# Boost_CNV.net
KiCad netlist of a schematic drawn in Altium Designer
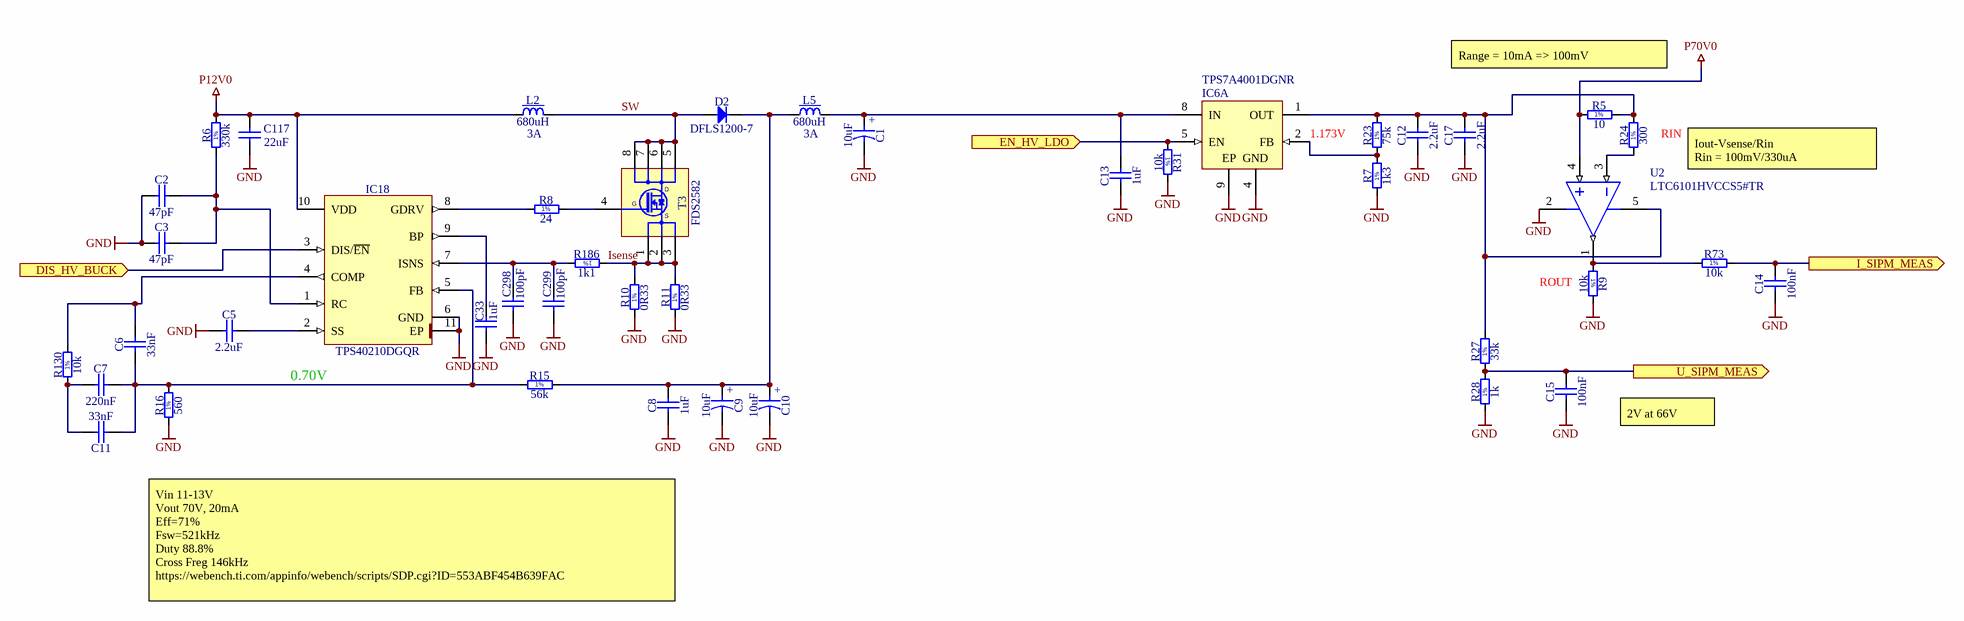
[diagram p0: Boost_CNV.SchDoc]

(export (version "E")
  (design (tool "Eeschema 10.0.6"))
  (components
    (comp (ref "C1")
      (value "10uF")
      (footprint "CAPAE830X1020N")
      (description "10uF, 100V, 1.5R")
      (fields
        (field (name "PART NUMBER") "CAE830-1020_10UF_100V_20%")
        (field (name "VOLTAGE") "100V")
        (field (name "AUTHOR") "CERN DEM JLC")
      )
      (libsource (lib "LIBRARY_SCH") (part "CAP_ELECTRO_SMD_F_10u_100V"))
    )
    (comp (ref "C2")
      (value "47pF")
      (footprint "CAPC1005X55N")
      (description "Non-polarised capacitor")
      (fields
        (field (name "PART NUMBER") "CC0402_47PF_50V_5%_C0G")
        (field (name "VOLTAGE") "50V")
        (field (name "AUTHOR") "CERN DEM JLC")
      )
      (libsource (lib "Capacitors") (part "Capacitor - non polarized"))
    )
    (comp (ref "C3")
      (value "47pF")
      (footprint "CAPC1005X55N")
      (description "Non-polarised capacitor")
      (fields
        (field (name "PART NUMBER") "CC0402_47PF_50V_5%_C0G")
        (field (name "VOLTAGE") "50V")
        (field (name "AUTHOR") "CERN DEM JLC")
      )
      (libsource (lib "Capacitors") (part "Capacitor - non polarized"))
    )
    (comp (ref "C5")
      (value "2.2uF")
      (footprint "CAPC2012X135N")
      (description "Non-polarised capacitor")
      (fields
        (field (name "PART NUMBER") "CC0805_2.2UF_16V_10%_X7R")
        (field (name "VOLTAGE") "16V")
        (field (name "AUTHOR") "CERN DEM JLC")
      )
      (libsource (lib "Capacitors") (part "Capacitor - non polarized"))
    )
    (comp (ref "C6")
      (value "33nF")
      (footprint "CAPC2012X135N")
      (description "Non-polarised capacitor")
      (fields
        (field (name "PART NUMBER") "CC0805_33NF_25V_10%_X7R")
        (field (name "VOLTAGE") "25V")
        (field (name "AUTHOR") "CERN DEM JLC")
      )
      (libsource (lib "Capacitors") (part "Capacitor - non polarized"))
    )
    (comp (ref "C7")
      (value "220nF")
      (footprint "CAPC2012X135N")
      (description "Non-polarised capacitor")
      (fields
        (field (name "PART NUMBER") "CC0805_220NF_50V_10%_X7R")
        (field (name "VOLTAGE") "50V")
        (field (name "AUTHOR") "CERN DEM JLC")
      )
      (libsource (lib "Capacitors") (part "Capacitor - non polarized"))
    )
    (comp (ref "C8")
      (value "1uF")
      (footprint "CAPC2013X145N")
      (description "Non-polarised capacitor")
      (fields
        (field (name "PART NUMBER") "CC0805_1UF_100V_10%_X7S")
        (field (name "VOLTAGE") "100V")
        (field (name "AUTHOR") "CERN DEM JLC")
      )
      (libsource (lib "Capacitors") (part "Capacitor - non polarized"))
    )
    (comp (ref "C9")
      (value "10uF")
      (footprint "CAPAE830X1020N")
      (description "10uF, 100V, 1.5R")
      (fields
        (field (name "PART NUMBER") "CAE830-1020_10UF_100V_20%")
        (field (name "VOLTAGE") "100V")
        (field (name "AUTHOR") "CERN DEM JLC")
      )
      (libsource (lib "LIBRARY_SCH") (part "CAP_ELECTRO_SMD_F_10u_100V"))
    )
    (comp (ref "C10")
      (value "10uF")
      (footprint "CAPAE830X1020N")
      (description "10uF, 100V, 1.5R")
      (fields
        (field (name "PART NUMBER") "CAE830-1020_10UF_100V_20%")
        (field (name "VOLTAGE") "100V")
        (field (name "AUTHOR") "CERN DEM JLC")
      )
      (libsource (lib "LIBRARY_SCH") (part "CAP_ELECTRO_SMD_F_10u_100V"))
    )
    (comp (ref "C11")
      (value "33nF")
      (footprint "CAPC2012X135N")
      (description "Non-polarised capacitor")
      (fields
        (field (name "PART NUMBER") "CC0805_33NF_25V_10%_X7R")
        (field (name "VOLTAGE") "25V")
        (field (name "AUTHOR") "CERN DEM JLC")
      )
      (libsource (lib "Capacitors") (part "Capacitor - non polarized"))
    )
    (comp (ref "C12")
      (value "2.2uF")
      (footprint "CAPC3225X230N")
      (description "Non-polarised capacitor")
      (fields
        (field (name "PART NUMBER") "CC1210_2.2UF_100V_10%_X7R_MURATA_GCJ32DR72A225KA01L")
        (field (name "VOLTAGE") "100V")
        (field (name "AUTHOR") "CERN DEM JLC")
      )
      (libsource (lib "Capacitors") (part "Capacitor - non polarized"))
    )
    (comp (ref "C13")
      (value "1uF")
      (footprint "CAPC2013X145N")
      (description "Non-polarised capacitor")
      (fields
        (field (name "PART NUMBER") "CC0805_1UF_100V_10%_X7S")
        (field (name "VOLTAGE") "100V")
        (field (name "AUTHOR") "CERN DEM JLC")
      )
      (libsource (lib "Capacitors") (part "Capacitor - non polarized"))
    )
    (comp (ref "C14")
      (value "100nF")
      (footprint "CAPC1005X55N")
      (description "Non-polarised capacitor")
      (fields
        (field (name "PART NUMBER") "CC0402_100NF_16V_10%_X7R")
        (field (name "VOLTAGE") "16V")
        (field (name "AUTHOR") "CERN DEM JLC")
      )
      (libsource (lib "Capacitors") (part "Capacitor - non polarized"))
    )
    (comp (ref "C15")
      (value "100nF")
      (footprint "CAPC1005X55N")
      (description "Non-polarised capacitor")
      (fields
        (field (name "PART NUMBER") "CC0402_100NF_16V_10%_X7R")
        (field (name "VOLTAGE") "16V")
        (field (name "AUTHOR") "CERN DEM JLC")
      )
      (libsource (lib "Capacitors") (part "Capacitor - non polarized"))
    )
    (comp (ref "C17")
      (value "2.2uF")
      (footprint "CAPC3225X230N")
      (description "Non-polarised capacitor")
      (fields
        (field (name "PART NUMBER") "CC1210_2.2UF_100V_10%_X7R_MURATA_GCJ32DR72A225KA01L")
        (field (name "VOLTAGE") "100V")
        (field (name "AUTHOR") "CERN DEM JLC")
      )
      (libsource (lib "Capacitors") (part "Capacitor - non polarized"))
    )
    (comp (ref "C33")
      (value "1uF")
      (footprint "CAPC1608X87N")
      (description "Non-polarised capacitor")
      (fields
        (field (name "PART NUMBER") "CC0603_1UF_16V_10%_X7R")
        (field (name "VOLTAGE") "16V")
        (field (name "AUTHOR") "CERN DEM JLC")
      )
      (libsource (lib "Capacitors") (part "Capacitor - non polarized"))
    )
    (comp (ref "C117")
      (value "22uF")
      (footprint "CAPC3216X180N")
      (description "Non-polarised capacitor")
      (fields
        (field (name "PART NUMBER") "CC1206_22UF_10V_10%_X7R")
        (field (name "VOLTAGE") "10V")
        (field (name "AUTHOR") "CERN DEM JLC")
      )
      (libsource (lib "Capacitors") (part "Capacitor - non polarized"))
    )
    (comp (ref "C298")
      (value "100pF")
      (footprint "CAPC1608X87N")
      (description "Non-polarised capacitor")
      (fields
        (field (name "PART NUMBER") "CC0603_100PF_50V_5%_NP0")
        (field (name "VOLTAGE") "50V")
        (field (name "AUTHOR") "CERN DEM JLC")
      )
      (libsource (lib "Capacitors") (part "Capacitor - non polarized"))
    )
    (comp (ref "C299")
      (value "100pF")
      (footprint "CAPC1608X87N")
      (description "Non-polarised capacitor")
      (fields
        (field (name "PART NUMBER") "CC0603_100PF_50V_5%_NP0")
        (field (name "VOLTAGE") "50V")
        (field (name "AUTHOR") "CERN DEM JLC")
      )
      (libsource (lib "Capacitors") (part "Capacitor - non polarized"))
    )
    (comp (ref "D2")
      (value "DFLS1200-7")
      (footprint "DIODES-INC_POWERDI123")
      (description "Diode")
      (fields
        (field (name "VOLTAGE") "200V")
        (field (name "POWER") "1A")
        (field (name "AUTHOR") "CERN DEM JLC")
      )
      (libsource (lib "ICs And Semiconductors") (part "Diode"))
    )
    (comp (ref "IC6")
      (value "TPS7A4001DGNR")
      (footprint "DGN0008B_M")
      (fields (field (name "MANUFACTURER") "Texas Instruments"))
      (libsource (lib "Altium Content Vault") (part "TI-TPS7A4X01DGN8-1880X1750TP"))
    )
    (comp (ref "IC18")
      (value "TPS40210DGQR")
      (footprint "SOP50P490X110-11N-R157X188")
      (description "Wide-Input Voltage (4.5V to 52V) Input Current Mode Boost Controller")
      (fields (field (name "MANUFACTURER") "TEXAS INSTRUMENTS") (field (name "AUTHOR") "CERN DEM JLC"))
      (libsource (lib "ICs And Semiconductors") (part "TPS40210"))
    )
    (comp (ref "L2")
      (value "680uH")
      (footprint "IND_EPCOS_B82476A1")
      (description "680uH, 3A, 0.17R")
      (fields
        (field (name "PART NUMBER") "IND_680UH_20%_COILCRAFT_DO3340P-684MLB")
        (field (name "POWER") "3A")
        (field (name "TOLERANCE") "±20%")
        (field (name "AUTHOR") "GK")
      )
      (libsource (lib "Inductors & Transformers") (part "Inductor With Magnetic core"))
    )
    (comp (ref "L5")
      (value "680uH")
      (footprint "IND_EPCOS_B82476A1")
      (description "680uH, 3A, 0.17R")
      (fields
        (field (name "PART NUMBER") "IND_680UH_20%_COILCRAFT_DO3340P-684MLB")
        (field (name "POWER") "3A")
        (field (name "TOLERANCE") "±20%")
        (field (name "AUTHOR") "GK")
      )
      (libsource (lib "Inductors & Transformers") (part "Inductor With Magnetic core"))
    )
    (comp (ref "R5")
      (value "10")
      (footprint "RESC3216X65N")
      (description "Resistor - 1%")
      (fields
        (field (name "PART NUMBER") "R1206_10R_1%_0.25W_200PPM")
        (field (name "POWER") "0.25W")
        (field (name "AUTHOR") "CERN DEM JLC")
      )
      (libsource (lib "Resistors") (part "Resistor - 1%"))
    )
    (comp (ref "R6")
      (value "330k")
      (footprint "RESC1608X55N")
      (description "Resistor - 1%")
      (fields
        (field (name "PART NUMBER") "R0603_330K_1%_0.1W_100PPM")
        (field (name "POWER") "0.1W")
        (field (name "AUTHOR") "CERN DEM JLC")
      )
      (libsource (lib "Resistors") (part "Resistor - 1%"))
    )
    (comp (ref "R7")
      (value "1k3")
      (footprint "RESC1608X55N")
      (description "Resistor - 1%")
      (fields
        (field (name "PART NUMBER") "R0603_1K3_1%_0.1W_100PPM")
        (field (name "POWER") "0.1W")
        (field (name "AUTHOR") "CERN DEM JLC")
      )
      (libsource (lib "Resistors") (part "Resistor - 1%"))
    )
    (comp (ref "R8")
      (value "24")
      (footprint "RESC1608X55N")
      (description "Resistor - 1%")
      (fields
        (field (name "PART NUMBER") "R0603_24R_1%_0.1W_100PPM")
        (field (name "POWER") "0.1W")
        (field (name "AUTHOR") "CERN DEM JLC")
      )
      (libsource (lib "Resistors") (part "Resistor - 1%"))
    )
    (comp (ref "R9")
      (value "10k")
      (footprint "RESC1005X40N")
      (description "Resistor - 1%")
      (fields
        (field (name "PART NUMBER") "R0402_10K_1%_0.0625W_100PPM")
        (field (name "POWER") "0.0625W")
        (field (name "AUTHOR") "CERN DEM JLC")
      )
      (libsource (lib "Resistors") (part "Resistor - 1%"))
    )
    (comp (ref "R10")
      (value "0R33")
      (footprint "RESC3216X65N")
      (description "Resistor - 1%")
      (fields
        (field (name "PART NUMBER") "R1206_0R33_1%_0.5W_600PPM")
        (field (name "POWER") "0.5W")
        (field (name "AUTHOR") "CERN DEM JMW")
      )
      (libsource (lib "Resistors") (part "Resistor - 1%"))
    )
    (comp (ref "R11")
      (value "0R33")
      (footprint "RESC3216X65N")
      (description "Resistor - 1%")
      (fields
        (field (name "PART NUMBER") "R1206_0R33_1%_0.5W_600PPM")
        (field (name "POWER") "0.5W")
        (field (name "AUTHOR") "CERN DEM JMW")
      )
      (libsource (lib "Resistors") (part "Resistor - 1%"))
    )
    (comp (ref "R15")
      (value "56k")
      (footprint "RESC1608X55N")
      (description "Resistor - 1%")
      (fields
        (field (name "PART NUMBER") "R0603_56K_1%_0.1W_100PPM")
        (field (name "POWER") "0.1W")
        (field (name "AUTHOR") "CERN DEM JLC")
      )
      (libsource (lib "Resistors") (part "Resistor - 1%"))
    )
    (comp (ref "R16")
      (value "560")
      (footprint "RESC1608X55N")
      (description "Resistor - 1%")
      (fields
        (field (name "PART NUMBER") "R0603_560R_1%_0.1W_100PPM")
        (field (name "POWER") "0.1W")
        (field (name "AUTHOR") "CERN DEM JLC")
      )
      (libsource (lib "Resistors") (part "Resistor - 1%"))
    )
    (comp (ref "R23")
      (value "75k")
      (footprint "RESC1608X55N")
      (description "Resistor - 1%")
      (fields
        (field (name "PART NUMBER") "R0603_75K_1%_0.1W_100PPM")
        (field (name "POWER") "0.1W")
        (field (name "AUTHOR") "CERN DEM JLC")
      )
      (libsource (lib "Resistors") (part "Resistor - 1%"))
    )
    (comp (ref "R24")
      (value "300")
      (footprint "RESC1005X40N")
      (description "Resistor - 1%")
      (fields
        (field (name "PART NUMBER") "R0402_300R_1%_0.0625W_100PPM")
        (field (name "POWER") "0.0625W")
        (field (name "AUTHOR") "CERN DEM JLC")
      )
      (libsource (lib "Resistors") (part "Resistor - 1%"))
    )
    (comp (ref "R27")
      (value "33k")
      (footprint "RESC2012X60N")
      (description "Resistor - 1%")
      (fields
        (field (name "PART NUMBER") "R0805_33K_1%_0.125W_100PPM")
        (field (name "POWER") "0.125W")
        (field (name "AUTHOR") "CERN DEM JLC")
      )
      (libsource (lib "Resistors") (part "Resistor - 1%"))
    )
    (comp (ref "R28")
      (value "1k")
      (footprint "RESC1005X40N")
      (description "Resistor - 1%")
      (fields
        (field (name "PART NUMBER") "R0402_1K_1%_0.0625W_100PPM")
        (field (name "POWER") "0.0625W")
        (field (name "AUTHOR") "CERN DEM JLC")
      )
      (libsource (lib "Resistors") (part "Resistor - 1%"))
    )
    (comp (ref "R31")
      (value "10k")
      (footprint "RESC1005X40N")
      (description "Resistor - 1%")
      (fields
        (field (name "PART NUMBER") "R0402_10K_1%_0.0625W_100PPM")
        (field (name "POWER") "0.0625W")
        (field (name "AUTHOR") "CERN DEM JLC")
      )
      (libsource (lib "Resistors") (part "Resistor - 1%"))
    )
    (comp (ref "R73")
      (value "10k")
      (footprint "RESC1005X40N")
      (description "Resistor - 1%")
      (fields
        (field (name "PART NUMBER") "R0402_10K_1%_0.0625W_100PPM")
        (field (name "POWER") "0.0625W")
        (field (name "AUTHOR") "CERN DEM JLC")
      )
      (libsource (lib "Resistors") (part "Resistor - 1%"))
    )
    (comp (ref "R130")
      (value "10k")
      (footprint "RESC1005X40N")
      (description "Resistor - 1%")
      (fields
        (field (name "PART NUMBER") "R0402_10K_1%_0.0625W_100PPM")
        (field (name "POWER") "0.0625W")
        (field (name "AUTHOR") "CERN DEM JLC")
      )
      (libsource (lib "Resistors") (part "Resistor - 1%"))
    )
    (comp (ref "R186")
      (value "1k1")
      (footprint "RESC1608X55N")
      (description "Resistor - 1%")
      (fields
        (field (name "PART NUMBER") "R0603_1K1_1%_0.1W_100PPM")
        (field (name "POWER") "0.1W")
        (field (name "AUTHOR") "CERN DEM JLC")
      )
      (libsource (lib "Resistors") (part "Resistor - 1%"))
    )
    (comp (ref "T3")
      (value "FDS2582")
      (footprint "SOIC127P600X175-8N")
      (description "150V 4.1A N-Channel PowerTrench® MOSFET")
      (fields (field (name "MANUFACTURER") "FAIRCHILD SEMICONDUCTOR") (field (name "AUTHOR") "CERN DEM JLC"))
      (libsource (lib "ICs And Semiconductors") (part "FDS2582"))
    )
    (comp (ref "U2")
      (value "LTC6101HVCCS5#TR")
      (footprint "LT-S5-5-TSOT-23_M")
      (fields
        (field (name "LINEAR TECHNOLOGY PART NUMBER") "LTC6101HV")
        (field (name "MANUFACTURER") "Linear Technology")
      )
      (libsource (lib "Altium Content Vault") (part "LT-LT6106-LTC6101HV-5"))
    )
  )
  (nets
    (net (code "1") (name "/DIS_HV_BUCK") (class "Default")
      (node (ref "IC18") (pin "3") (pinfunction "DIS/~{EN}_3") (pintype "input"))
    )
    (net (code "2") (name "/EN_HV_LDO") (class "Default")
      (node (ref "IC6") (pin "5") (pinfunction "EN_5") (pintype "input"))
      (node (ref "R31") (pin "1") (pinfunction "1_1") (pintype "passive"))
    )
    (net (code "3") (name "/I_SIPM_MEAS") (class "Default")
      (node (ref "C14") (pin "2") (pinfunction "2_2") (pintype "passive"))
      (node (ref "R73") (pin "2") (pinfunction "2_2") (pintype "passive"))
    )
    (net (code "4") (name "/Isense") (class "Default")
      (node (ref "R10") (pin "2") (pinfunction "2_2") (pintype "passive"))
      (node (ref "R11") (pin "2") (pinfunction "2_2") (pintype "passive"))
      (node (ref "R186") (pin "1") (pinfunction "1_1") (pintype "passive"))
      (node (ref "T3") (pin "1") (pinfunction "S_1") (pintype "passive"))
      (node (ref "T3") (pin "2") (pinfunction "S_2") (pintype "passive"))
      (node (ref "T3") (pin "3") (pinfunction "S_3") (pintype "passive"))
    )
    (net (code "5") (name "/SW") (class "Default")
      (node (ref "D2") (pin "2") (pinfunction "A_2") (pintype "passive"))
      (node (ref "L2") (pin "2") (pinfunction "2_2") (pintype "passive"))
      (node (ref "T3") (pin "5") (pinfunction "D_5") (pintype "passive"))
      (node (ref "T3") (pin "6") (pinfunction "D_6") (pintype "passive"))
      (node (ref "T3") (pin "7") (pinfunction "D_7") (pintype "passive"))
      (node (ref "T3") (pin "8") (pinfunction "D_8") (pintype "passive"))
    )
    (net (code "6") (name "/U_SIPM_MEAS") (class "Default")
      (node (ref "C15") (pin "2") (pinfunction "2_2") (pintype "passive"))
      (node (ref "R27") (pin "1") (pinfunction "1_1") (pintype "passive"))
      (node (ref "R28") (pin "2") (pinfunction "2_2") (pintype "passive"))
    )
    (net (code "7") (name "GND") (class "Default")
      (node (ref "C1") (pin "2") (pinfunction "2_2") (pintype "passive"))
      (node (ref "C10") (pin "2") (pinfunction "2_2") (pintype "passive"))
      (node (ref "C117") (pin "1") (pinfunction "1_1") (pintype "passive"))
      (node (ref "C12") (pin "1") (pinfunction "1_1") (pintype "passive"))
      (node (ref "C13") (pin "1") (pinfunction "1_1") (pintype "passive"))
      (node (ref "C14") (pin "1") (pinfunction "1_1") (pintype "passive"))
      (node (ref "C15") (pin "1") (pinfunction "1_1") (pintype "passive"))
      (node (ref "C17") (pin "1") (pinfunction "1_1") (pintype "passive"))
      (node (ref "C2") (pin "1") (pinfunction "1_1") (pintype "passive"))
      (node (ref "C298") (pin "1") (pinfunction "1_1") (pintype "passive"))
      (node (ref "C299") (pin "1") (pinfunction "1_1") (pintype "passive"))
      (node (ref "C3") (pin "1") (pinfunction "1_1") (pintype "passive"))
      (node (ref "C33") (pin "1") (pinfunction "1_1") (pintype "passive"))
      (node (ref "C5") (pin "1") (pinfunction "1_1") (pintype "passive"))
      (node (ref "C8") (pin "1") (pinfunction "1_1") (pintype "passive"))
      (node (ref "C9") (pin "2") (pinfunction "2_2") (pintype "passive"))
      (node (ref "IC18") (pin "11") (pinfunction "EP_11") (pintype "power_in"))
      (node (ref "IC18") (pin "6") (pinfunction "GND_6") (pintype "power_in"))
      (node (ref "IC6") (pin "4") (pinfunction "GND_4") (pintype "power_in"))
      (node (ref "IC6") (pin "9") (pinfunction "EP_9") (pintype "power_in"))
      (node (ref "R10") (pin "1") (pinfunction "1_1") (pintype "passive"))
      (node (ref "R11") (pin "1") (pinfunction "1_1") (pintype "passive"))
      (node (ref "R16") (pin "1") (pinfunction "1_1") (pintype "passive"))
      (node (ref "R28") (pin "1") (pinfunction "1_1") (pintype "passive"))
      (node (ref "R31") (pin "2") (pinfunction "2_2") (pintype "passive"))
      (node (ref "R7") (pin "1") (pinfunction "1_1") (pintype "passive"))
      (node (ref "R9") (pin "2") (pinfunction "2_2") (pintype "passive"))
      (node (ref "U2") (pin "2") (pinfunction "V-_2") (pintype "power_in"))
    )
    (net (code "8") (name "Net-(C11-Pad2)") (class "Default")
      (node (ref "C11") (pin "2") (pinfunction "2_2") (pintype "passive"))
      (node (ref "C7") (pin "1") (pinfunction "1_1") (pintype "passive"))
      (node (ref "R130") (pin "1") (pinfunction "1_1") (pintype "passive"))
    )
    (net (code "9") (name "Net-(D2-C)") (class "Default")
      (node (ref "C10") (pin "1") (pinfunction "1_1") (pintype "passive"))
      (node (ref "C8") (pin "2") (pinfunction "2_2") (pintype "passive"))
      (node (ref "C9") (pin "1") (pinfunction "1_1") (pintype "passive"))
      (node (ref "D2") (pin "1") (pinfunction "C_1") (pintype "passive"))
      (node (ref "L5") (pin "1") (pinfunction "1_1") (pintype "passive"))
      (node (ref "R15") (pin "2") (pinfunction "2_2") (pintype "passive"))
    )
    (net (code "10") (name "Net-(IC6A-FB)") (class "Default")
      (node (ref "IC6") (pin "2") (pinfunction "FB_2") (pintype "input"))
      (node (ref "R23") (pin "1") (pinfunction "1_1") (pintype "passive"))
      (node (ref "R7") (pin "2") (pinfunction "2_2") (pintype "passive"))
    )
    (net (code "11") (name "Net-(IC6A-IN)") (class "Default")
      (node (ref "C1") (pin "1") (pinfunction "1_1") (pintype "passive"))
      (node (ref "C13") (pin "2") (pinfunction "2_2") (pintype "passive"))
      (node (ref "IC6") (pin "8") (pinfunction "IN_8") (pintype "power_in"))
      (node (ref "L5") (pin "2") (pinfunction "2_2") (pintype "passive"))
    )
    (net (code "12") (name "Net-(IC6A-OUT)") (class "Default")
      (node (ref "C12") (pin "2") (pinfunction "2_2") (pintype "passive"))
      (node (ref "C17") (pin "2") (pinfunction "2_2") (pintype "passive"))
      (node (ref "IC6") (pin "1") (pinfunction "OUT_1") (pintype "power_in"))
      (node (ref "R23") (pin "2") (pinfunction "2_2") (pintype "passive"))
      (node (ref "R24") (pin "2") (pinfunction "2_2") (pintype "passive"))
      (node (ref "R27") (pin "2") (pinfunction "2_2") (pintype "passive"))
      (node (ref "R5") (pin "2") (pinfunction "2_2") (pintype "passive"))
      (node (ref "U2") (pin "5") (pinfunction "V+_5") (pintype "power_in"))
    )
    (net (code "13") (name "Net-(IC18-BP)") (class "Default")
      (node (ref "C33") (pin "2") (pinfunction "2_2") (pintype "passive"))
      (node (ref "IC18") (pin "9") (pinfunction "BP_9") (pintype "output"))
    )
    (net (code "14") (name "Net-(IC18-COMP)") (class "Default")
      (node (ref "C6") (pin "2") (pinfunction "2_2") (pintype "passive"))
      (node (ref "IC18") (pin "4") (pinfunction "COMP_4") (pintype "output"))
      (node (ref "R130") (pin "2") (pinfunction "2_2") (pintype "passive"))
    )
    (net (code "15") (name "Net-(IC18-FB)") (class "Default")
      (node (ref "C11") (pin "1") (pinfunction "1_1") (pintype "passive"))
      (node (ref "C6") (pin "1") (pinfunction "1_1") (pintype "passive"))
      (node (ref "C7") (pin "2") (pinfunction "2_2") (pintype "passive"))
      (node (ref "IC18") (pin "5") (pinfunction "FB_5") (pintype "input"))
      (node (ref "R15") (pin "1") (pinfunction "1_1") (pintype "passive"))
      (node (ref "R16") (pin "2") (pinfunction "2_2") (pintype "passive"))
    )
    (net (code "16") (name "Net-(IC18-GDRV)") (class "Default")
      (node (ref "IC18") (pin "8") (pinfunction "GDRV_8") (pintype "output"))
      (node (ref "R8") (pin "1") (pinfunction "1_1") (pintype "passive"))
    )
    (net (code "17") (name "Net-(IC18-ISNS)") (class "Default")
      (node (ref "C298") (pin "2") (pinfunction "2_2") (pintype "passive"))
      (node (ref "C299") (pin "2") (pinfunction "2_2") (pintype "passive"))
      (node (ref "IC18") (pin "7") (pinfunction "ISNS_7") (pintype "input"))
      (node (ref "R186") (pin "2") (pinfunction "2_2") (pintype "passive"))
    )
    (net (code "18") (name "Net-(IC18-RC)") (class "Default")
      (node (ref "C2") (pin "2") (pinfunction "2_2") (pintype "passive"))
      (node (ref "C3") (pin "2") (pinfunction "2_2") (pintype "passive"))
      (node (ref "IC18") (pin "1") (pinfunction "RC_1") (pintype "input"))
      (node (ref "R6") (pin "1") (pinfunction "1_1") (pintype "passive"))
    )
    (net (code "19") (name "Net-(IC18-SS)") (class "Default")
      (node (ref "C5") (pin "2") (pinfunction "2_2") (pintype "passive"))
      (node (ref "IC18") (pin "2") (pinfunction "SS_2") (pintype "input"))
    )
    (net (code "20") (name "Net-(T3-G)") (class "Default")
      (node (ref "R8") (pin "2") (pinfunction "2_2") (pintype "passive"))
      (node (ref "T3") (pin "4") (pinfunction "G_4") (pintype "passive"))
    )
    (net (code "21") (name "Net-(U2--IN)") (class "Default")
      (node (ref "R24") (pin "1") (pinfunction "1_1") (pintype "passive"))
      (node (ref "U2") (pin "3") (pinfunction "-IN_3") (pintype "input"))
    )
    (net (code "22") (name "Net-(U2-OUT)") (class "Default")
      (node (ref "R73") (pin "1") (pinfunction "1_1") (pintype "passive"))
      (node (ref "R9") (pin "1") (pinfunction "1_1") (pintype "passive"))
      (node (ref "U2") (pin "1") (pinfunction "OUT_1") (pintype "output"))
    )
    (net (code "23") (name "P12V0") (class "Default")
      (node (ref "C117") (pin "2") (pinfunction "2_2") (pintype "passive"))
      (node (ref "IC18") (pin "10") (pinfunction "VDD_10") (pintype "power_in"))
      (node (ref "L2") (pin "1") (pinfunction "1_1") (pintype "passive"))
      (node (ref "R6") (pin "2") (pinfunction "2_2") (pintype "passive"))
    )
    (net (code "24") (name "P70V0") (class "Default")
      (node (ref "R5") (pin "1") (pinfunction "1_1") (pintype "passive"))
      (node (ref "U2") (pin "4") (pinfunction "+IN_4") (pintype "input"))
    )
  )
)
